# Earphone-2.net
KiCad netlist of a schematic drawn in Altium Designer
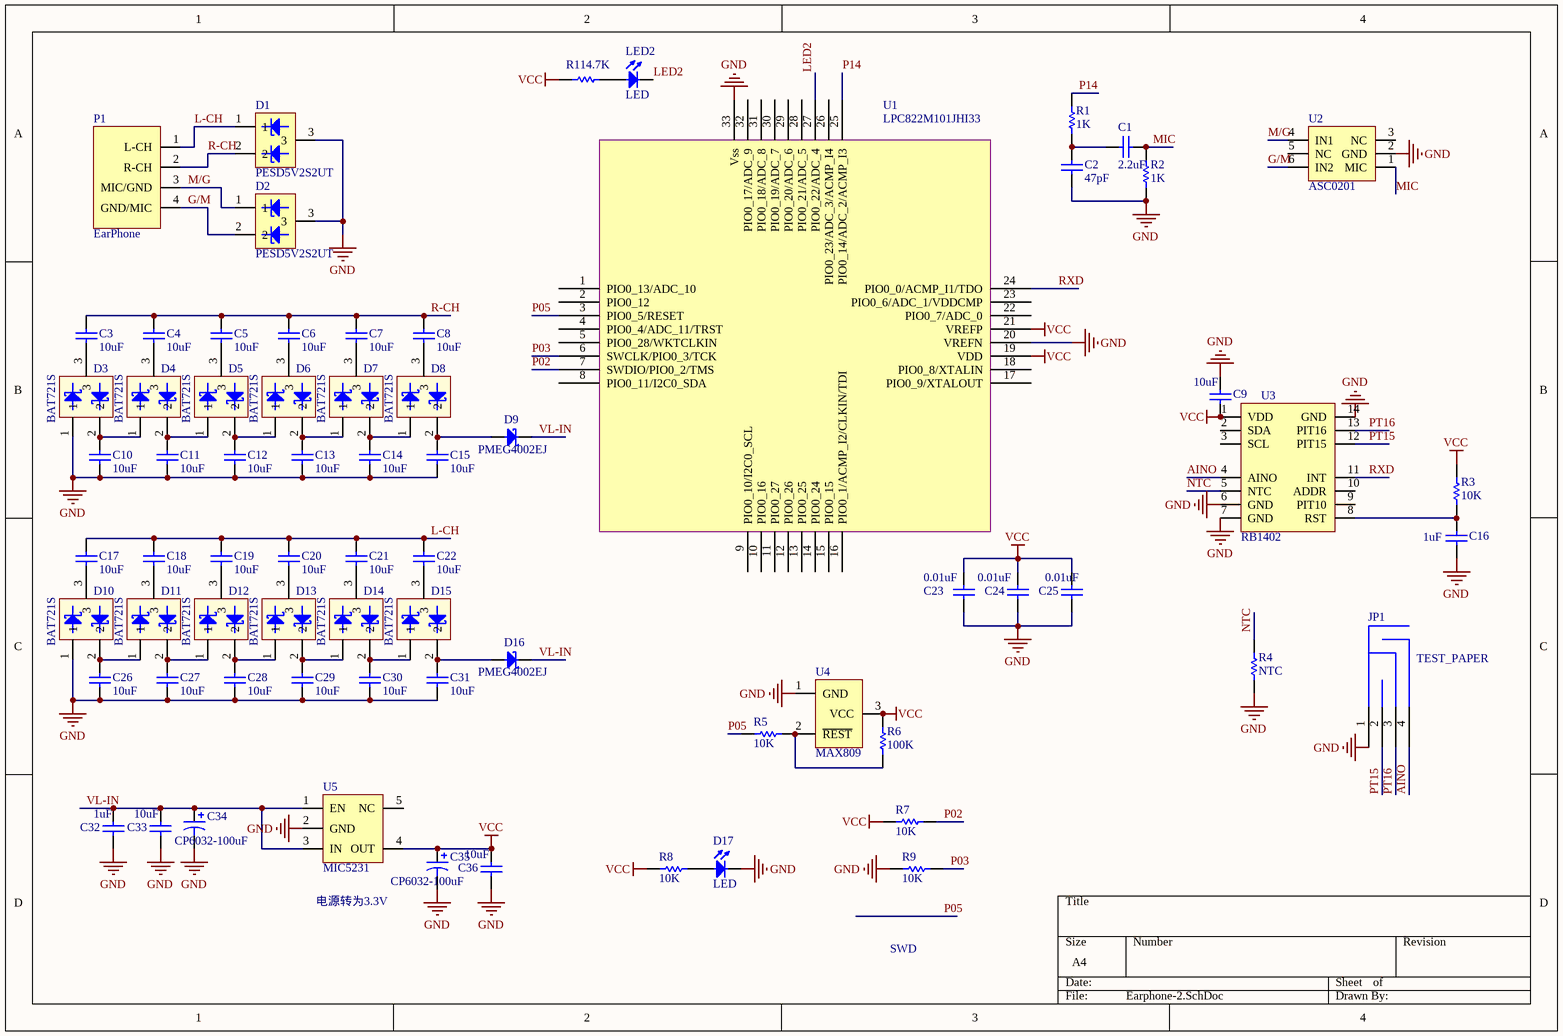
[diagram p0: Earphone-2.SchDoc]

(export (version "E")
  (design (tool "Eeschema 10.0.6"))
  (components
    (comp (ref "C1") (value "2.2uF") (footprint "0402C") (libsource (lib "Schlib1") (part "CAP")))
    (comp (ref "C2") (value "47pF") (footprint "0402C") (libsource (lib "Schlib1") (part "CAP")))
    (comp (ref "C3") (value "10uF") (footprint "0402C") (libsource (lib "Schlib1") (part "CAP")))
    (comp (ref "C4") (value "10uF") (footprint "0402C") (libsource (lib "Schlib1") (part "CAP")))
    (comp (ref "C5") (value "10uF") (footprint "0402C") (libsource (lib "Schlib1") (part "CAP")))
    (comp (ref "C6") (value "10uF") (footprint "0402C") (libsource (lib "Schlib1") (part "CAP")))
    (comp (ref "C7") (value "10uF") (footprint "0402C") (libsource (lib "Schlib1") (part "CAP")))
    (comp (ref "C8") (value "10uF") (footprint "0402C") (libsource (lib "Schlib1") (part "CAP")))
    (comp (ref "C9") (value "10uF") (footprint "0402C") (libsource (lib "Schlib1") (part "CAP")))
    (comp (ref "C10") (value "10uF") (footprint "0402C") (libsource (lib "Schlib1") (part "CAP")))
    (comp (ref "C11") (value "10uF") (footprint "0402C") (libsource (lib "Schlib1") (part "CAP")))
    (comp (ref "C12") (value "10uF") (footprint "0402C") (libsource (lib "Schlib1") (part "CAP")))
    (comp (ref "C13") (value "10uF") (footprint "0402C") (libsource (lib "Schlib1") (part "CAP")))
    (comp (ref "C14") (value "10uF") (footprint "0402C") (libsource (lib "Schlib1") (part "CAP")))
    (comp (ref "C15") (value "10uF") (footprint "0402C") (libsource (lib "Schlib1") (part "CAP")))
    (comp (ref "C16") (value "1uF") (footprint "0402C") (libsource (lib "Schlib1") (part "CAP")))
    (comp (ref "C17") (value "10uF") (footprint "0402C") (libsource (lib "Schlib1") (part "CAP")))
    (comp (ref "C18") (value "10uF") (footprint "0402C") (libsource (lib "Schlib1") (part "CAP")))
    (comp (ref "C19") (value "10uF") (footprint "0402C") (libsource (lib "Schlib1") (part "CAP")))
    (comp (ref "C20") (value "10uF") (footprint "0402C") (libsource (lib "Schlib1") (part "CAP")))
    (comp (ref "C21") (value "10uF") (footprint "0402C") (libsource (lib "Schlib1") (part "CAP")))
    (comp (ref "C22") (value "10uF") (footprint "0402C") (libsource (lib "Schlib1") (part "CAP")))
    (comp (ref "C23") (value "0.01uF") (footprint "0402C") (libsource (lib "Schlib1") (part "CAP")))
    (comp (ref "C24") (value "0.01uF") (footprint "0402C") (libsource (lib "Schlib1") (part "CAP")))
    (comp (ref "C25") (value "0.01uF") (footprint "0402C") (libsource (lib "Schlib1") (part "CAP")))
    (comp (ref "C26") (value "10uF") (footprint "0402C") (libsource (lib "Schlib1") (part "CAP")))
    (comp (ref "C27") (value "10uF") (footprint "0402C") (libsource (lib "Schlib1") (part "CAP")))
    (comp (ref "C28") (value "10uF") (footprint "0402C") (libsource (lib "Schlib1") (part "CAP")))
    (comp (ref "C29") (value "10uF") (footprint "0402C") (libsource (lib "Schlib1") (part "CAP")))
    (comp (ref "C30") (value "10uF") (footprint "0402C") (libsource (lib "Schlib1") (part "CAP")))
    (comp (ref "C31") (value "10uF") (footprint "0402C") (libsource (lib "Schlib1") (part "CAP")))
    (comp (ref "C32") (value "1uF") (footprint "0402C") (libsource (lib "Schlib1") (part "CAP")))
    (comp (ref "C33") (value "10uF") (footprint "0402C") (libsource (lib "Schlib1") (part "CAP")))
    (comp (ref "C34")
      (value "CP6032-100uF")
      (footprint "T3216-18[A]")
      (libsource (lib "Schlib1") (part "CAP POL2"))
    )
    (comp (ref "C35")
      (value "CP6032-100uF")
      (footprint "T3216-18[A]")
      (libsource (lib "Schlib1") (part "CAP POL2"))
    )
    (comp (ref "C36") (value "10uF") (footprint "0402C") (libsource (lib "Schlib1") (part "CAP")))
    (comp (ref "D1")
      (value "PESD5V2S2UT")
      (footprint "SOT23")
      (description "SOT23")
      (libsource (lib "Schlib1") (part "PESD5V2S2UT"))
    )
    (comp (ref "D2")
      (value "PESD5V2S2UT")
      (footprint "SOT23")
      (description "SOT23")
      (libsource (lib "Schlib1") (part "PESD5V2S2UT"))
    )
    (comp (ref "D3")
      (value "BAT721S")
      (footprint "SOT23")
      (description "SOT23")
      (libsource (lib "Schlib1") (part "BAT721S"))
    )
    (comp (ref "D4")
      (value "BAT721S")
      (footprint "SOT23")
      (description "SOT23")
      (libsource (lib "Schlib1") (part "BAT721S"))
    )
    (comp (ref "D5")
      (value "BAT721S")
      (footprint "SOT23")
      (description "SOT23")
      (libsource (lib "Schlib1") (part "BAT721S"))
    )
    (comp (ref "D6")
      (value "BAT721S")
      (footprint "SOT23")
      (description "SOT23")
      (libsource (lib "Schlib1") (part "BAT721S"))
    )
    (comp (ref "D7")
      (value "BAT721S")
      (footprint "SOT23")
      (description "SOT23")
      (libsource (lib "Schlib1") (part "BAT721S"))
    )
    (comp (ref "D8")
      (value "BAT721S")
      (footprint "SOT23")
      (description "SOT23")
      (libsource (lib "Schlib1") (part "BAT721S"))
    )
    (comp (ref "D9")
      (value "PMEG4002EJ")
      (footprint "SOD323")
      (description "SOD323F")
      (libsource (lib "Schlib1") (part "PMEG4002EJ"))
    )
    (comp (ref "D10")
      (value "BAT721S")
      (footprint "SOT23")
      (description "SOT23")
      (libsource (lib "Schlib1") (part "BAT721S"))
    )
    (comp (ref "D11")
      (value "BAT721S")
      (footprint "SOT23")
      (description "SOT23")
      (libsource (lib "Schlib1") (part "BAT721S"))
    )
    (comp (ref "D12")
      (value "BAT721S")
      (footprint "SOT23")
      (description "SOT23")
      (libsource (lib "Schlib1") (part "BAT721S"))
    )
    (comp (ref "D13")
      (value "BAT721S")
      (footprint "SOT23")
      (description "SOT23")
      (libsource (lib "Schlib1") (part "BAT721S"))
    )
    (comp (ref "D14")
      (value "BAT721S")
      (footprint "SOT23")
      (description "SOT23")
      (libsource (lib "Schlib1") (part "BAT721S"))
    )
    (comp (ref "D15")
      (value "BAT721S")
      (footprint "SOT23")
      (description "SOT23")
      (libsource (lib "Schlib1") (part "BAT721S"))
    )
    (comp (ref "D16")
      (value "PMEG4002EJ")
      (footprint "SOD323")
      (description "SOD323F")
      (libsource (lib "Schlib1") (part "PMEG4002EJ"))
    )
    (comp (ref "D17") (value "LED") (footprint "0603L") (libsource (lib "Schlib1") (part "LED")))
    (comp (ref "JP1")
      (value "TEST_PAPER")
      (footprint "TEST_PAPER")
      (libsource (lib "Schlib1") (part "TEST_PAPER"))
    )
    (comp (ref "LED2") (value "LED") (footprint "0603L") (libsource (lib "Schlib1") (part "LED")))
    (comp (ref "P1") (value "EarPhone") (footprint "EarPhone") (libsource (lib "Schlib1") (part "EarPhone")))
    (comp (ref "R1") (value "1K") (footprint "0402R") (libsource (lib "Schlib1") (part "RES")))
    (comp (ref "R2") (value "1K") (footprint "0402R") (libsource (lib "Schlib1") (part "RES")))
    (comp (ref "R3") (value "10K") (footprint "0402R") (libsource (lib "Schlib1") (part "RES")))
    (comp (ref "R4") (value "NTC") (footprint "0603R") (libsource (lib "Schlib1") (part "RES")))
    (comp (ref "R5") (value "10K") (footprint "0402R") (libsource (lib "Schlib1") (part "RES")))
    (comp (ref "R6") (value "100K") (footprint "0402R") (libsource (lib "Schlib1") (part "RES")))
    (comp (ref "R7") (value "10K") (footprint "0402R") (libsource (lib "Schlib1") (part "RES")))
    (comp (ref "R8") (value "10K") (footprint "0402R") (libsource (lib "Schlib1") (part "RES")))
    (comp (ref "R9") (value "10K") (footprint "0402R") (libsource (lib "Schlib1") (part "RES")))
    (comp (ref "R11") (value "4.7K") (footprint "0402R") (libsource (lib "Schlib1") (part "RES")))
    (comp (ref "U1")
      (value "LPC822M101JHI33")
      (footprint "QFN50P500X500X100-33N")
      (libsource (lib "Schlib1") (part "LPC822M101JHI33"))
    )
    (comp (ref "U2")
      (value "ASC0201")
      (footprint "SOT23-6")
      (description "SOT23-6")
      (libsource (lib "Schlib1") (part "ASC0201"))
    )
    (comp (ref "U3") (value "RB1402") (footprint "RB1402") (libsource (lib "Schlib1") (part "RB1402")))
    (comp (ref "U4")
      (value "MAX809")
      (footprint "SOT23")
      (description "SOT23")
      (libsource (lib "Schlib1") (part "MAX809"))
    )
    (comp (ref "U5") (value "MIC5231") (footprint "SOT23-5") (libsource (lib "Schlib1") (part "MIC5231")))
  )
  (nets
    (net (code "1") (name "/AINO") (class "Default")
      (node (ref "JP1") (pin "4") (pinfunction "P_4") (pintype "passive"))
      (node (ref "U3") (pin "4") (pinfunction "AINO_4") (pintype "passive"))
    )
    (net (code "2") (name "/G{slash}M") (class "Default")
      (node (ref "D2") (pin "2") (pinfunction "2_2") (pintype "passive"))
      (node (ref "P1") (pin "4") (pinfunction "GND/MIC_4") (pintype "passive"))
      (node (ref "U2") (pin "6") (pinfunction "IN2_6") (pintype "passive"))
    )
    (net (code "3") (name "/L-CH") (class "Default")
      (node (ref "C17") (pin "2") (pinfunction "2_2") (pintype "passive"))
      (node (ref "C18") (pin "2") (pinfunction "2_2") (pintype "passive"))
      (node (ref "C19") (pin "2") (pinfunction "2_2") (pintype "passive"))
      (node (ref "C20") (pin "2") (pinfunction "2_2") (pintype "passive"))
      (node (ref "C21") (pin "2") (pinfunction "2_2") (pintype "passive"))
      (node (ref "C22") (pin "2") (pinfunction "2_2") (pintype "passive"))
      (node (ref "D1") (pin "1") (pinfunction "1_1") (pintype "passive"))
      (node (ref "P1") (pin "1") (pinfunction "L-CH_1") (pintype "passive"))
    )
    (net (code "4") (name "/LED2") (class "Default")
      (node (ref "LED2") (pin "2") (pinfunction "K_2") (pintype "passive"))
      (node (ref "U1") (pin "27") (pinfunction "PIO0_22/ADC_4_27") (pintype "passive"))
    )
    (net (code "5") (name "/MIC") (class "Default")
      (node (ref "C1") (pin "1") (pinfunction "1_1") (pintype "passive"))
      (node (ref "R2") (pin "1") (pinfunction "1_1") (pintype "passive"))
      (node (ref "U2") (pin "1") (pinfunction "MIC_1") (pintype "passive"))
    )
    (net (code "6") (name "/M{slash}G") (class "Default")
      (node (ref "D2") (pin "1") (pinfunction "1_1") (pintype "passive"))
      (node (ref "P1") (pin "3") (pinfunction "MIC/GND_3") (pintype "passive"))
      (node (ref "U2") (pin "4") (pinfunction "IN1_4") (pintype "passive"))
    )
    (net (code "7") (name "/NTC") (class "Default")
      (node (ref "R4") (pin "2") (pinfunction "2_2") (pintype "passive"))
      (node (ref "U3") (pin "5") (pinfunction "NTC_5") (pintype "passive"))
    )
    (net (code "8") (name "/P02") (class "Default")
      (node (ref "R7") (pin "2") (pinfunction "2_2") (pintype "passive"))
      (node (ref "U1") (pin "7") (pinfunction "SWDIO/PIO0_2/TMS_7") (pintype "passive"))
    )
    (net (code "9") (name "/P03") (class "Default")
      (node (ref "R9") (pin "1") (pinfunction "1_1") (pintype "passive"))
      (node (ref "U1") (pin "6") (pinfunction "SWCLK/PIO0_3/TCK_6") (pintype "passive"))
    )
    (net (code "10") (name "/P05") (class "Default")
      (node (ref "R5") (pin "1") (pinfunction "1_1") (pintype "passive"))
      (node (ref "U1") (pin "3") (pinfunction "PIO0_5/RESET_3") (pintype "passive"))
    )
    (net (code "11") (name "/P14") (class "Default")
      (node (ref "R1") (pin "1") (pinfunction "1_1") (pintype "passive"))
      (node (ref "U1") (pin "25") (pinfunction "PIO0_14/ADC_2/ACMP_I3_25") (pintype "passive"))
    )
    (net (code "12") (name "/PT15") (class "Default")
      (node (ref "JP1") (pin "2") (pinfunction "PC10_2") (pintype "passive"))
      (node (ref "U3") (pin "12") (pinfunction "PIT15_12") (pintype "passive"))
    )
    (net (code "13") (name "/PT16") (class "Default")
      (node (ref "JP1") (pin "3") (pinfunction "NOP_3") (pintype "passive"))
      (node (ref "U3") (pin "13") (pinfunction "PIT16_13") (pintype "passive"))
    )
    (net (code "14") (name "/R-CH") (class "Default")
      (node (ref "C3") (pin "2") (pinfunction "2_2") (pintype "passive"))
      (node (ref "C4") (pin "2") (pinfunction "2_2") (pintype "passive"))
      (node (ref "C5") (pin "2") (pinfunction "2_2") (pintype "passive"))
      (node (ref "C6") (pin "2") (pinfunction "2_2") (pintype "passive"))
      (node (ref "C7") (pin "2") (pinfunction "2_2") (pintype "passive"))
      (node (ref "C8") (pin "2") (pinfunction "2_2") (pintype "passive"))
      (node (ref "D1") (pin "2") (pinfunction "2_2") (pintype "passive"))
      (node (ref "P1") (pin "2") (pinfunction "R-CH_2") (pintype "passive"))
    )
    (net (code "15") (name "/RXD") (class "Default")
      (node (ref "U1") (pin "24") (pinfunction "PIO0_0/ACMP_I1/TDO_24") (pintype "passive"))
      (node (ref "U3") (pin "11") (pinfunction "INT_11") (pintype "passive"))
    )
    (net (code "16") (name "/VL-IN") (class "Default")
      (node (ref "C32") (pin "2") (pinfunction "2_2") (pintype "passive"))
      (node (ref "C33") (pin "2") (pinfunction "2_2") (pintype "passive"))
      (node (ref "C34") (pin "1") (pinfunction "1_1") (pintype "passive"))
      (node (ref "D16") (pin "1") (pinfunction "1_1") (pintype "passive"))
      (node (ref "D9") (pin "1") (pinfunction "1_1") (pintype "passive"))
      (node (ref "U5") (pin "1") (pinfunction "EN_1") (pintype "passive"))
      (node (ref "U5") (pin "3") (pinfunction "IN_3") (pintype "passive"))
    )
    (net (code "17") (name "GND") (class "Default")
      (node (ref "C10") (pin "1") (pinfunction "1_1") (pintype "passive"))
      (node (ref "C11") (pin "1") (pinfunction "1_1") (pintype "passive"))
      (node (ref "C12") (pin "1") (pinfunction "1_1") (pintype "passive"))
      (node (ref "C13") (pin "1") (pinfunction "1_1") (pintype "passive"))
      (node (ref "C14") (pin "1") (pinfunction "1_1") (pintype "passive"))
      (node (ref "C15") (pin "1") (pinfunction "1_1") (pintype "passive"))
      (node (ref "C16") (pin "1") (pinfunction "1_1") (pintype "passive"))
      (node (ref "C2") (pin "1") (pinfunction "1_1") (pintype "passive"))
      (node (ref "C23") (pin "1") (pinfunction "1_1") (pintype "passive"))
      (node (ref "C24") (pin "1") (pinfunction "1_1") (pintype "passive"))
      (node (ref "C25") (pin "1") (pinfunction "1_1") (pintype "passive"))
      (node (ref "C26") (pin "1") (pinfunction "1_1") (pintype "passive"))
      (node (ref "C27") (pin "1") (pinfunction "1_1") (pintype "passive"))
      (node (ref "C28") (pin "1") (pinfunction "1_1") (pintype "passive"))
      (node (ref "C29") (pin "1") (pinfunction "1_1") (pintype "passive"))
      (node (ref "C30") (pin "1") (pinfunction "1_1") (pintype "passive"))
      (node (ref "C31") (pin "1") (pinfunction "1_1") (pintype "passive"))
      (node (ref "C32") (pin "1") (pinfunction "1_1") (pintype "passive"))
      (node (ref "C33") (pin "1") (pinfunction "1_1") (pintype "passive"))
      (node (ref "C34") (pin "2") (pinfunction "2_2") (pintype "passive"))
      (node (ref "C35") (pin "2") (pinfunction "2_2") (pintype "passive"))
      (node (ref "C36") (pin "1") (pinfunction "1_1") (pintype "passive"))
      (node (ref "C9") (pin "2") (pinfunction "2_2") (pintype "passive"))
      (node (ref "D1") (pin "3") (pinfunction "3_3") (pintype "passive"))
      (node (ref "D10") (pin "1") (pinfunction "1_1") (pintype "passive"))
      (node (ref "D17") (pin "2") (pinfunction "K_2") (pintype "passive"))
      (node (ref "D2") (pin "3") (pinfunction "3_3") (pintype "passive"))
      (node (ref "D3") (pin "1") (pinfunction "1_1") (pintype "passive"))
      (node (ref "JP1") (pin "1") (pinfunction "N_1") (pintype "passive"))
      (node (ref "R2") (pin "2") (pinfunction "2_2") (pintype "passive"))
      (node (ref "R4") (pin "1") (pinfunction "1_1") (pintype "passive"))
      (node (ref "R9") (pin "2") (pinfunction "2_2") (pintype "passive"))
      (node (ref "U1") (pin "20") (pinfunction "VREFN_20") (pintype "passive"))
      (node (ref "U1") (pin "33") (pinfunction "Vss_33") (pintype "passive"))
      (node (ref "U2") (pin "2") (pinfunction "GND_2") (pintype "passive"))
      (node (ref "U3") (pin "14") (pinfunction "GND_14") (pintype "passive"))
      (node (ref "U3") (pin "6") (pinfunction "GND_6") (pintype "passive"))
      (node (ref "U3") (pin "7") (pinfunction "GND_7") (pintype "passive"))
      (node (ref "U4") (pin "1") (pinfunction "GND_1") (pintype "passive"))
      (node (ref "U5") (pin "2") (pinfunction "GND_2") (pintype "passive"))
    )
    (net (code "18") (name "Net-(C1-Pad2)") (class "Default")
      (node (ref "C1") (pin "2") (pinfunction "2_2") (pintype "passive"))
      (node (ref "C2") (pin "2") (pinfunction "2_2") (pintype "passive"))
      (node (ref "R1") (pin "2") (pinfunction "2_2") (pintype "passive"))
    )
    (net (code "19") (name "Net-(C3-Pad1)") (class "Default")
      (node (ref "C3") (pin "1") (pinfunction "1_1") (pintype "passive"))
      (node (ref "D3") (pin "3") (pinfunction "3_3") (pintype "passive"))
    )
    (net (code "20") (name "Net-(C4-Pad1)") (class "Default")
      (node (ref "C4") (pin "1") (pinfunction "1_1") (pintype "passive"))
      (node (ref "D4") (pin "3") (pinfunction "3_3") (pintype "passive"))
    )
    (net (code "21") (name "Net-(C5-Pad1)") (class "Default")
      (node (ref "C5") (pin "1") (pinfunction "1_1") (pintype "passive"))
      (node (ref "D5") (pin "3") (pinfunction "3_3") (pintype "passive"))
    )
    (net (code "22") (name "Net-(C6-Pad1)") (class "Default")
      (node (ref "C6") (pin "1") (pinfunction "1_1") (pintype "passive"))
      (node (ref "D6") (pin "3") (pinfunction "3_3") (pintype "passive"))
    )
    (net (code "23") (name "Net-(C7-Pad1)") (class "Default")
      (node (ref "C7") (pin "1") (pinfunction "1_1") (pintype "passive"))
      (node (ref "D7") (pin "3") (pinfunction "3_3") (pintype "passive"))
    )
    (net (code "24") (name "Net-(C8-Pad1)") (class "Default")
      (node (ref "C8") (pin "1") (pinfunction "1_1") (pintype "passive"))
      (node (ref "D8") (pin "3") (pinfunction "3_3") (pintype "passive"))
    )
    (net (code "25") (name "Net-(C10-Pad2)") (class "Default")
      (node (ref "C10") (pin "2") (pinfunction "2_2") (pintype "passive"))
      (node (ref "D3") (pin "2") (pinfunction "2_2") (pintype "passive"))
      (node (ref "D4") (pin "1") (pinfunction "1_1") (pintype "passive"))
    )
    (net (code "26") (name "Net-(C11-Pad2)") (class "Default")
      (node (ref "C11") (pin "2") (pinfunction "2_2") (pintype "passive"))
      (node (ref "D4") (pin "2") (pinfunction "2_2") (pintype "passive"))
      (node (ref "D5") (pin "1") (pinfunction "1_1") (pintype "passive"))
    )
    (net (code "27") (name "Net-(C12-Pad2)") (class "Default")
      (node (ref "C12") (pin "2") (pinfunction "2_2") (pintype "passive"))
      (node (ref "D5") (pin "2") (pinfunction "2_2") (pintype "passive"))
      (node (ref "D6") (pin "1") (pinfunction "1_1") (pintype "passive"))
    )
    (net (code "28") (name "Net-(C13-Pad2)") (class "Default")
      (node (ref "C13") (pin "2") (pinfunction "2_2") (pintype "passive"))
      (node (ref "D6") (pin "2") (pinfunction "2_2") (pintype "passive"))
      (node (ref "D7") (pin "1") (pinfunction "1_1") (pintype "passive"))
    )
    (net (code "29") (name "Net-(C14-Pad2)") (class "Default")
      (node (ref "C14") (pin "2") (pinfunction "2_2") (pintype "passive"))
      (node (ref "D7") (pin "2") (pinfunction "2_2") (pintype "passive"))
      (node (ref "D8") (pin "1") (pinfunction "1_1") (pintype "passive"))
    )
    (net (code "30") (name "Net-(C15-Pad2)") (class "Default")
      (node (ref "C15") (pin "2") (pinfunction "2_2") (pintype "passive"))
      (node (ref "D8") (pin "2") (pinfunction "2_2") (pintype "passive"))
      (node (ref "D9") (pin "2") (pinfunction "2_2") (pintype "passive"))
    )
    (net (code "31") (name "Net-(C17-Pad1)") (class "Default")
      (node (ref "C17") (pin "1") (pinfunction "1_1") (pintype "passive"))
      (node (ref "D10") (pin "3") (pinfunction "3_3") (pintype "passive"))
    )
    (net (code "32") (name "Net-(C18-Pad1)") (class "Default")
      (node (ref "C18") (pin "1") (pinfunction "1_1") (pintype "passive"))
      (node (ref "D11") (pin "3") (pinfunction "3_3") (pintype "passive"))
    )
    (net (code "33") (name "Net-(C19-Pad1)") (class "Default")
      (node (ref "C19") (pin "1") (pinfunction "1_1") (pintype "passive"))
      (node (ref "D12") (pin "3") (pinfunction "3_3") (pintype "passive"))
    )
    (net (code "34") (name "Net-(C20-Pad1)") (class "Default")
      (node (ref "C20") (pin "1") (pinfunction "1_1") (pintype "passive"))
      (node (ref "D13") (pin "3") (pinfunction "3_3") (pintype "passive"))
    )
    (net (code "35") (name "Net-(C21-Pad1)") (class "Default")
      (node (ref "C21") (pin "1") (pinfunction "1_1") (pintype "passive"))
      (node (ref "D14") (pin "3") (pinfunction "3_3") (pintype "passive"))
    )
    (net (code "36") (name "Net-(C22-Pad1)") (class "Default")
      (node (ref "C22") (pin "1") (pinfunction "1_1") (pintype "passive"))
      (node (ref "D15") (pin "3") (pinfunction "3_3") (pintype "passive"))
    )
    (net (code "37") (name "Net-(C26-Pad2)") (class "Default")
      (node (ref "C26") (pin "2") (pinfunction "2_2") (pintype "passive"))
      (node (ref "D10") (pin "2") (pinfunction "2_2") (pintype "passive"))
      (node (ref "D11") (pin "1") (pinfunction "1_1") (pintype "passive"))
    )
    (net (code "38") (name "Net-(C27-Pad2)") (class "Default")
      (node (ref "C27") (pin "2") (pinfunction "2_2") (pintype "passive"))
      (node (ref "D11") (pin "2") (pinfunction "2_2") (pintype "passive"))
      (node (ref "D12") (pin "1") (pinfunction "1_1") (pintype "passive"))
    )
    (net (code "39") (name "Net-(C28-Pad2)") (class "Default")
      (node (ref "C28") (pin "2") (pinfunction "2_2") (pintype "passive"))
      (node (ref "D12") (pin "2") (pinfunction "2_2") (pintype "passive"))
      (node (ref "D13") (pin "1") (pinfunction "1_1") (pintype "passive"))
    )
    (net (code "40") (name "Net-(C29-Pad2)") (class "Default")
      (node (ref "C29") (pin "2") (pinfunction "2_2") (pintype "passive"))
      (node (ref "D13") (pin "2") (pinfunction "2_2") (pintype "passive"))
      (node (ref "D14") (pin "1") (pinfunction "1_1") (pintype "passive"))
    )
    (net (code "41") (name "Net-(C30-Pad2)") (class "Default")
      (node (ref "C30") (pin "2") (pinfunction "2_2") (pintype "passive"))
      (node (ref "D14") (pin "2") (pinfunction "2_2") (pintype "passive"))
      (node (ref "D15") (pin "1") (pinfunction "1_1") (pintype "passive"))
    )
    (net (code "42") (name "Net-(C31-Pad2)") (class "Default")
      (node (ref "C31") (pin "2") (pinfunction "2_2") (pintype "passive"))
      (node (ref "D15") (pin "2") (pinfunction "2_2") (pintype "passive"))
      (node (ref "D16") (pin "2") (pinfunction "2_2") (pintype "passive"))
    )
    (net (code "43") (name "Net-(D17-A)") (class "Default")
      (node (ref "D17") (pin "1") (pinfunction "A_1") (pintype "passive"))
      (node (ref "R8") (pin "2") (pinfunction "2_2") (pintype "passive"))
    )
    (net (code "44") (name "Net-(LED2-A)") (class "Default")
      (node (ref "LED2") (pin "1") (pinfunction "A_1") (pintype "passive"))
      (node (ref "R11") (pin "2") (pinfunction "2_2") (pintype "passive"))
    )
    (net (code "45") (name "Net-(U3-RST)") (class "Default")
      (node (ref "C16") (pin "2") (pinfunction "2_2") (pintype "passive"))
      (node (ref "R3") (pin "1") (pinfunction "1_1") (pintype "passive"))
      (node (ref "U3") (pin "8") (pinfunction "RST_8") (pintype "passive"))
    )
    (net (code "46") (name "Net-(U4-~{REST})") (class "Default")
      (node (ref "R5") (pin "2") (pinfunction "2_2") (pintype "passive"))
      (node (ref "R6") (pin "1") (pinfunction "1_1") (pintype "passive"))
      (node (ref "U4") (pin "2") (pinfunction "~{REST}_2") (pintype "passive"))
    )
    (net (code "47") (name "VCC") (class "Default")
      (node (ref "C23") (pin "2") (pinfunction "2_2") (pintype "passive"))
      (node (ref "C24") (pin "2") (pinfunction "2_2") (pintype "passive"))
      (node (ref "C25") (pin "2") (pinfunction "2_2") (pintype "passive"))
      (node (ref "C35") (pin "1") (pinfunction "1_1") (pintype "passive"))
      (node (ref "C36") (pin "2") (pinfunction "2_2") (pintype "passive"))
      (node (ref "C9") (pin "1") (pinfunction "1_1") (pintype "passive"))
      (node (ref "R11") (pin "1") (pinfunction "1_1") (pintype "passive"))
      (node (ref "R3") (pin "2") (pinfunction "2_2") (pintype "passive"))
      (node (ref "R6") (pin "2") (pinfunction "2_2") (pintype "passive"))
      (node (ref "R7") (pin "1") (pinfunction "1_1") (pintype "passive"))
      (node (ref "R8") (pin "1") (pinfunction "1_1") (pintype "passive"))
      (node (ref "U1") (pin "19") (pinfunction "VDD_19") (pintype "passive"))
      (node (ref "U1") (pin "21") (pinfunction "VREFP_21") (pintype "passive"))
      (node (ref "U3") (pin "1") (pinfunction "VDD_1") (pintype "passive"))
      (node (ref "U4") (pin "3") (pinfunction "VCC_3") (pintype "passive"))
      (node (ref "U5") (pin "4") (pinfunction "OUT_4") (pintype "passive"))
    )
    (net (code "48") (name "unconnected-(U1-PIO0_1{slash}ACMP_I2{slash}CLKIN{slash}TDI-Pad16)") (class "Default")
      (node (ref "U1") (pin "16") (pinfunction "PIO0_1/ACMP_I2/CLKIN/TDI_16") (pintype "passive"))
    )
    (net (code "49") (name "unconnected-(U1-PIO0_4{slash}ADC_11{slash}TRST-Pad4)") (class "Default")
      (node (ref "U1") (pin "4") (pinfunction "PIO0_4/ADC_11/TRST_4") (pintype "passive"))
    )
    (net (code "50") (name "unconnected-(U1-PIO0_6{slash}ADC_1{slash}VDDCMP-Pad23)") (class "Default")
      (node (ref "U1") (pin "23") (pinfunction "PIO0_6/ADC_1/VDDCMP_23") (pintype "passive"))
    )
    (net (code "51") (name "unconnected-(U1-PIO0_7{slash}ADC_0-Pad22)") (class "Default")
      (node (ref "U1") (pin "22") (pinfunction "PIO0_7/ADC_0_22") (pintype "passive"))
    )
    (net (code "52") (name "unconnected-(U1-PIO0_8{slash}XTALIN-Pad18)") (class "Default")
      (node (ref "U1") (pin "18") (pinfunction "PIO0_8/XTALIN_18") (pintype "passive"))
    )
    (net (code "53") (name "unconnected-(U1-PIO0_9{slash}XTALOUT-Pad17)") (class "Default")
      (node (ref "U1") (pin "17") (pinfunction "PIO0_9/XTALOUT_17") (pintype "passive"))
    )
    (net (code "54") (name "unconnected-(U1-PIO0_10{slash}I2C0_SCL-Pad9)") (class "Default")
      (node (ref "U1") (pin "9") (pinfunction "PIO0_10/I2C0_SCL_9") (pintype "passive"))
    )
    (net (code "55") (name "unconnected-(U1-PIO0_11{slash}I2C0_SDA-Pad8)") (class "Default")
      (node (ref "U1") (pin "8") (pinfunction "PIO0_11/I2C0_SDA_8") (pintype "passive"))
    )
    (net (code "56") (name "unconnected-(U1-PIO0_12-Pad2)") (class "Default")
      (node (ref "U1") (pin "2") (pinfunction "PIO0_12_2") (pintype "passive"))
    )
    (net (code "57") (name "unconnected-(U1-PIO0_13{slash}ADC_10-Pad1)") (class "Default")
      (node (ref "U1") (pin "1") (pinfunction "PIO0_13/ADC_10_1") (pintype "passive"))
    )
    (net (code "58") (name "unconnected-(U1-PIO0_15-Pad15)") (class "Default")
      (node (ref "U1") (pin "15") (pinfunction "PIO0_15_15") (pintype "passive"))
    )
    (net (code "59") (name "unconnected-(U1-PIO0_16-Pad10)") (class "Default")
      (node (ref "U1") (pin "10") (pinfunction "PIO0_16_10") (pintype "passive"))
    )
    (net (code "60") (name "unconnected-(U1-PIO0_17{slash}ADC_9-Pad32)") (class "Default")
      (node (ref "U1") (pin "32") (pinfunction "PIO0_17/ADC_9_32") (pintype "passive"))
    )
    (net (code "61") (name "unconnected-(U1-PIO0_18{slash}ADC_8-Pad31)") (class "Default")
      (node (ref "U1") (pin "31") (pinfunction "PIO0_18/ADC_8_31") (pintype "passive"))
    )
    (net (code "62") (name "unconnected-(U1-PIO0_19{slash}ADC_7-Pad30)") (class "Default")
      (node (ref "U1") (pin "30") (pinfunction "PIO0_19/ADC_7_30") (pintype "passive"))
    )
    (net (code "63") (name "unconnected-(U1-PIO0_20{slash}ADC_6-Pad29)") (class "Default")
      (node (ref "U1") (pin "29") (pinfunction "PIO0_20/ADC_6_29") (pintype "passive"))
    )
    (net (code "64") (name "unconnected-(U1-PIO0_21{slash}ADC_5-Pad28)") (class "Default")
      (node (ref "U1") (pin "28") (pinfunction "PIO0_21/ADC_5_28") (pintype "passive"))
    )
    (net (code "65") (name "unconnected-(U1-PIO0_23{slash}ADC_3{slash}ACMP_I4-Pad26)") (class "Default")
      (node (ref "U1") (pin "26") (pinfunction "PIO0_23/ADC_3/ACMP_I4_26") (pintype "passive"))
    )
    (net (code "66") (name "unconnected-(U1-PIO0_24-Pad14)") (class "Default")
      (node (ref "U1") (pin "14") (pinfunction "PIO0_24_14") (pintype "passive"))
    )
    (net (code "67") (name "unconnected-(U1-PIO0_25-Pad13)") (class "Default")
      (node (ref "U1") (pin "13") (pinfunction "PIO0_25_13") (pintype "passive"))
    )
    (net (code "68") (name "unconnected-(U1-PIO0_26-Pad12)") (class "Default")
      (node (ref "U1") (pin "12") (pinfunction "PIO0_26_12") (pintype "passive"))
    )
    (net (code "69") (name "unconnected-(U1-PIO0_27-Pad11)") (class "Default")
      (node (ref "U1") (pin "11") (pinfunction "PIO0_27_11") (pintype "passive"))
    )
    (net (code "70") (name "unconnected-(U1-PIO0_28{slash}WKTCLKIN-Pad5)") (class "Default")
      (node (ref "U1") (pin "5") (pinfunction "PIO0_28/WKTCLKIN_5") (pintype "passive"))
    )
    (net (code "71") (name "unconnected-(U2-NC-Pad3)") (class "Default")
      (node (ref "U2") (pin "3") (pinfunction "NC_3") (pintype "passive"))
    )
    (net (code "72") (name "unconnected-(U2-NC-Pad5)") (class "Default")
      (node (ref "U2") (pin "5") (pinfunction "NC_5") (pintype "passive"))
    )
    (net (code "73") (name "unconnected-(U3-ADDR-Pad10)") (class "Default")
      (node (ref "U3") (pin "10") (pinfunction "ADDR_10") (pintype "passive"))
    )
    (net (code "74") (name "unconnected-(U3-PIT10-Pad9)") (class "Default")
      (node (ref "U3") (pin "9") (pinfunction "PIT10_9") (pintype "passive"))
    )
    (net (code "75") (name "unconnected-(U3-SCL-Pad3)") (class "Default")
      (node (ref "U3") (pin "3") (pinfunction "SCL_3") (pintype "passive"))
    )
    (net (code "76") (name "unconnected-(U3-SDA-Pad2)") (class "Default")
      (node (ref "U3") (pin "2") (pinfunction "SDA_2") (pintype "passive"))
    )
    (net (code "77") (name "unconnected-(U5-NC-Pad5)") (class "Default")
      (node (ref "U5") (pin "5") (pinfunction "NC_5") (pintype "passive"))
    )
  )
)
